# final_board.net
KiCad netlist of a schematic drawn in EAGLE
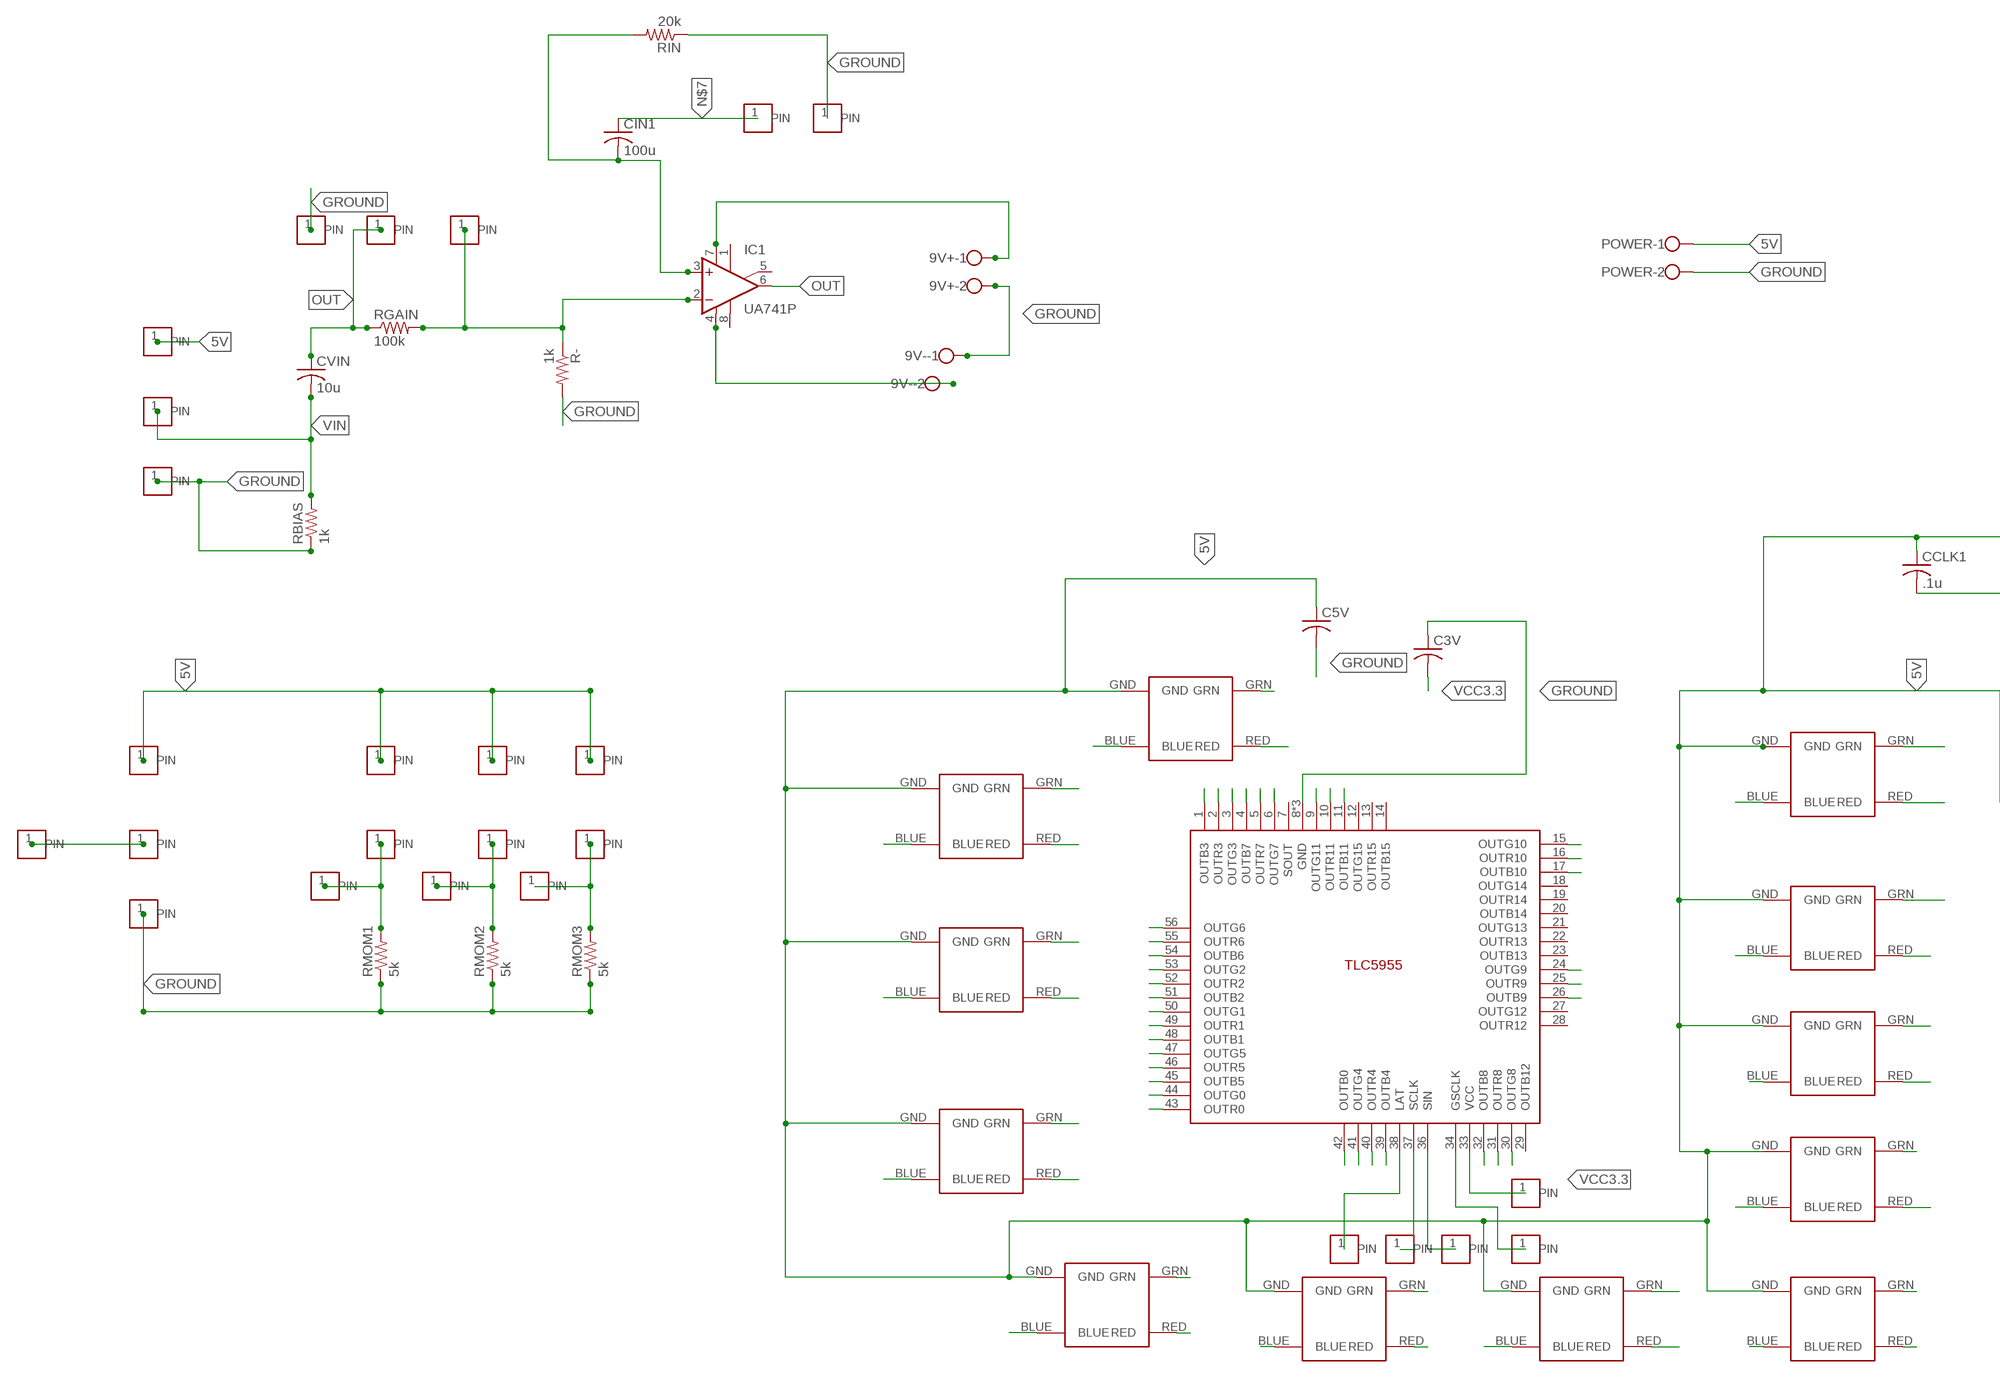
[diagram p0: schematic, sheet 1, part 1 of 2]
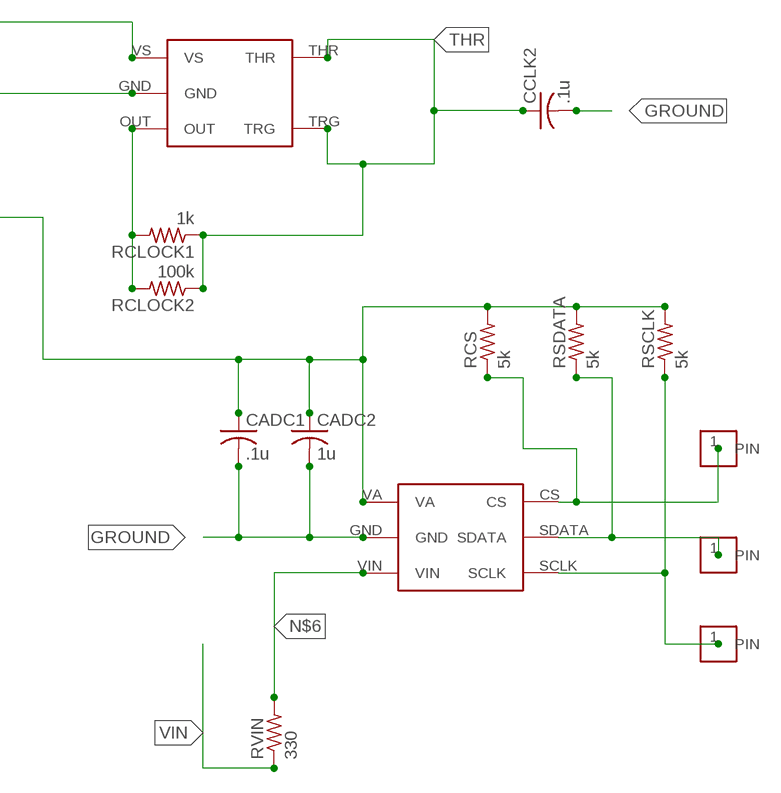
[diagram p1: schematic, sheet 1, part 2 of 2]

(export (version "E")
  (design (tool "Eeschema 10.0.6"))
  (components
    (comp (ref "3.3V")
      (value "HEADERPIN_1")
      (footprint "eagle-import:HEADERPIN_1")
      (libsource (lib "eagle-import") (part "HEADERPIN_1"))
    )
    (comp (ref "9V+")
      (value "W237-102")
      (footprint "eagle-import:W237-102")
      (fields (field (name "MPN") "237-102"))
      (libsource (lib "eagle-import") (part "W237-102"))
    )
    (comp (ref "9V-")
      (value "W237-102")
      (footprint "eagle-import:W237-102")
      (fields (field (name "MPN") "237-102"))
      (libsource (lib "eagle-import") (part "W237-102"))
    )
    (comp (ref "C3V")
      (value "C-USC0805")
      (footprint "eagle-import:C0805")
      (libsource (lib "eagle-import") (part "C-USC0805"))
    )
    (comp (ref "C5V")
      (value "C-USC0805")
      (footprint "eagle-import:C0805")
      (libsource (lib "eagle-import") (part "C-USC0805"))
    )
    (comp (ref "CADC1")
      (value ".1u")
      (footprint "eagle-import:C0805")
      (libsource (lib "eagle-import") (part "C-USC0805"))
    )
    (comp (ref "CADC2")
      (value "1u")
      (footprint "eagle-import:C0805")
      (libsource (lib "eagle-import") (part "C-USC0805"))
    )
    (comp (ref "CCLK1")
      (value ".1u")
      (footprint "eagle-import:C0805")
      (libsource (lib "eagle-import") (part "C-USC0805"))
    )
    (comp (ref "CCLK2")
      (value ".1u")
      (footprint "eagle-import:C0805")
      (libsource (lib "eagle-import") (part "C-USC0805"))
    )
    (comp (ref "CIN1")
      (value "100u")
      (footprint "eagle-import:C0805")
      (libsource (lib "eagle-import") (part "C-USC0805"))
    )
    (comp (ref "CS")
      (value "HEADERPIN_1")
      (footprint "eagle-import:HEADERPIN_1")
      (libsource (lib "eagle-import") (part "HEADERPIN_1"))
    )
    (comp (ref "CVIN")
      (value "10u")
      (footprint "eagle-import:C0805")
      (libsource (lib "eagle-import") (part "C-USC0805"))
    )
    (comp (ref "DATA")
      (value "HEADERPIN_1")
      (footprint "eagle-import:HEADERPIN_1")
      (libsource (lib "eagle-import") (part "HEADERPIN_1"))
    )
    (comp (ref "GSCLK")
      (value "HEADERPIN_1")
      (footprint "eagle-import:HEADERPIN_1")
      (libsource (lib "eagle-import") (part "HEADERPIN_1"))
    )
    (comp (ref "IC1")
      (value "UA741P")
      (footprint "eagle-import:DIL08")
      (libsource (lib "eagle-import") (part "741PUA"))
    )
    (comp (ref "INPUTGND")
      (value "HEADERPIN_1")
      (footprint "eagle-import:HEADERPIN_1")
      (libsource (lib "eagle-import") (part "HEADERPIN_1"))
    )
    (comp (ref "INPUTV")
      (value "HEADERPIN_1")
      (footprint "eagle-import:HEADERPIN_1")
      (libsource (lib "eagle-import") (part "HEADERPIN_1"))
    )
    (comp (ref "INT1")
      (value "HEADERPIN_1")
      (footprint "eagle-import:HEADERPIN_1")
      (libsource (lib "eagle-import") (part "HEADERPIN_1"))
    )
    (comp (ref "INT2")
      (value "HEADERPIN_1")
      (footprint "eagle-import:HEADERPIN_1")
      (libsource (lib "eagle-import") (part "HEADERPIN_1"))
    )
    (comp (ref "INT3")
      (value "HEADERPIN_1")
      (footprint "eagle-import:HEADERPIN_1")
      (libsource (lib "eagle-import") (part "HEADERPIN_1"))
    )
    (comp (ref "LAT")
      (value "HEADERPIN_1")
      (footprint "eagle-import:HEADERPIN_1")
      (libsource (lib "eagle-import") (part "HEADERPIN_1"))
    )
    (comp (ref "MOMA1")
      (value "HEADERPIN_1")
      (footprint "eagle-import:HEADERPIN_1")
      (libsource (lib "eagle-import") (part "HEADERPIN_1"))
    )
    (comp (ref "MOMA2")
      (value "HEADERPIN_1")
      (footprint "eagle-import:HEADERPIN_1")
      (libsource (lib "eagle-import") (part "HEADERPIN_1"))
    )
    (comp (ref "MOMA3")
      (value "HEADERPIN_1")
      (footprint "eagle-import:HEADERPIN_1")
      (libsource (lib "eagle-import") (part "HEADERPIN_1"))
    )
    (comp (ref "MOMB1")
      (value "HEADERPIN_1")
      (footprint "eagle-import:HEADERPIN_1")
      (libsource (lib "eagle-import") (part "HEADERPIN_1"))
    )
    (comp (ref "MOMB2")
      (value "HEADERPIN_1")
      (footprint "eagle-import:HEADERPIN_1")
      (libsource (lib "eagle-import") (part "HEADERPIN_1"))
    )
    (comp (ref "MOMB3")
      (value "HEADERPIN_1")
      (footprint "eagle-import:HEADERPIN_1")
      (libsource (lib "eagle-import") (part "HEADERPIN_1"))
    )
    (comp (ref "POTAMPGND")
      (value "HEADERPIN_1")
      (footprint "eagle-import:HEADERPIN_1")
      (libsource (lib "eagle-import") (part "HEADERPIN_1"))
    )
    (comp (ref "POTAMPVAL")
      (value "HEADERPIN_1")
      (footprint "eagle-import:HEADERPIN_1")
      (libsource (lib "eagle-import") (part "HEADERPIN_1"))
    )
    (comp (ref "POTAMPVCC")
      (value "HEADERPIN_1")
      (footprint "eagle-import:HEADERPIN_1")
      (libsource (lib "eagle-import") (part "HEADERPIN_1"))
    )
    (comp (ref "POTBIAS5V")
      (value "HEADERPIN_1")
      (footprint "eagle-import:HEADERPIN_1")
      (libsource (lib "eagle-import") (part "HEADERPIN_1"))
    )
    (comp (ref "POTBIASGND")
      (value "HEADERPIN_1")
      (footprint "eagle-import:HEADERPIN_1")
      (libsource (lib "eagle-import") (part "HEADERPIN_1"))
    )
    (comp (ref "POTBIASVAL")
      (value "HEADERPIN_1")
      (footprint "eagle-import:HEADERPIN_1")
      (libsource (lib "eagle-import") (part "HEADERPIN_1"))
    )
    (comp (ref "POTLVL5V")
      (value "HEADERPIN_1")
      (footprint "eagle-import:HEADERPIN_1")
      (libsource (lib "eagle-import") (part "HEADERPIN_1"))
    )
    (comp (ref "POTLVLGND")
      (value "HEADERPIN_1")
      (footprint "eagle-import:HEADERPIN_1")
      (libsource (lib "eagle-import") (part "HEADERPIN_1"))
    )
    (comp (ref "POTLVLVAL")
      (value "HEADERPIN_1")
      (footprint "eagle-import:HEADERPIN_1")
      (libsource (lib "eagle-import") (part "HEADERPIN_1"))
    )
    (comp (ref "POTLVLVAL2")
      (value "HEADERPIN_1")
      (footprint "eagle-import:HEADERPIN_1")
      (libsource (lib "eagle-import") (part "HEADERPIN_1"))
    )
    (comp (ref "POWER")
      (value "W237-102")
      (footprint "eagle-import:W237-102")
      (fields (field (name "MPN") "237-102"))
      (libsource (lib "eagle-import") (part "W237-102"))
    )
    (comp (ref "R-")
      (value "1k")
      (footprint "eagle-import:M0805")
      (libsource (lib "eagle-import") (part "R-US_M0805"))
    )
    (comp (ref "RBIAS")
      (value "1k")
      (footprint "eagle-import:M0805")
      (libsource (lib "eagle-import") (part "R-US_M0805"))
    )
    (comp (ref "RCLOCK1")
      (value "1k")
      (footprint "eagle-import:M0805")
      (libsource (lib "eagle-import") (part "R-US_M0805"))
    )
    (comp (ref "RCLOCK2")
      (value "100k")
      (footprint "eagle-import:M0805")
      (libsource (lib "eagle-import") (part "R-US_M0805"))
    )
    (comp (ref "RCS")
      (value "5k")
      (footprint "eagle-import:M0805")
      (libsource (lib "eagle-import") (part "R-US_M0805"))
    )
    (comp (ref "RGAIN")
      (value "100k")
      (footprint "eagle-import:M0805")
      (libsource (lib "eagle-import") (part "R-US_M0805"))
    )
    (comp (ref "RIN")
      (value "20k")
      (footprint "eagle-import:M0805")
      (libsource (lib "eagle-import") (part "R-US_M0805"))
    )
    (comp (ref "RMOM1")
      (value "5k")
      (footprint "eagle-import:M0805")
      (libsource (lib "eagle-import") (part "R-US_M0805"))
    )
    (comp (ref "RMOM2")
      (value "5k")
      (footprint "eagle-import:M0805")
      (libsource (lib "eagle-import") (part "R-US_M0805"))
    )
    (comp (ref "RMOM3")
      (value "5k")
      (footprint "eagle-import:M0805")
      (libsource (lib "eagle-import") (part "R-US_M0805"))
    )
    (comp (ref "RSCLK")
      (value "5k")
      (footprint "eagle-import:M0805")
      (libsource (lib "eagle-import") (part "R-US_M0805"))
    )
    (comp (ref "RSDATA")
      (value "5k")
      (footprint "eagle-import:M0805")
      (libsource (lib "eagle-import") (part "R-US_M0805"))
    )
    (comp (ref "RVIN")
      (value "330")
      (footprint "eagle-import:M0805")
      (libsource (lib "eagle-import") (part "R-US_M0805"))
    )
    (comp (ref "SCLK")
      (value "HEADERPIN_1")
      (footprint "eagle-import:HEADERPIN_1")
      (libsource (lib "eagle-import") (part "HEADERPIN_1"))
    )
    (comp (ref "SIN")
      (value "HEADERPIN_1")
      (footprint "eagle-import:HEADERPIN_1")
      (libsource (lib "eagle-import") (part "HEADERPIN_1"))
    )
    (comp (ref "SLK")
      (value "HEADERPIN_1")
      (footprint "eagle-import:HEADERPIN_1")
      (libsource (lib "eagle-import") (part "HEADERPIN_1"))
    )
    (comp (ref "TLC5955")
      (value "TLC5954")
      (footprint "eagle-import:TLC5955")
      (libsource (lib "eagle-import") (part "TLC5954"))
    )
    (comp (ref "U$1")
      (value "MIC1555")
      (footprint "eagle-import:SOT-23")
      (libsource (lib "eagle-import") (part "MIC1555"))
    )
    (comp (ref "U$2")
      (value "KINGSBRIGHT_LED_3.5X2.8")
      (footprint "eagle-import:KINGSBRIGHT_LED_3.5X2.8")
      (libsource (lib "eagle-import") (part "KINGSBRIGHT_LED_3.5X2.8"))
    )
    (comp (ref "U$3")
      (value "KINGSBRIGHT_LED_3.5X2.8")
      (footprint "eagle-import:KINGSBRIGHT_LED_3.5X2.8")
      (libsource (lib "eagle-import") (part "KINGSBRIGHT_LED_3.5X2.8"))
    )
    (comp (ref "U$4")
      (value "KINGSBRIGHT_LED_3.5X2.8")
      (footprint "eagle-import:KINGSBRIGHT_LED_3.5X2.8")
      (libsource (lib "eagle-import") (part "KINGSBRIGHT_LED_3.5X2.8"))
    )
    (comp (ref "U$5")
      (value "KINGSBRIGHT_LED_3.5X2.8")
      (footprint "eagle-import:KINGSBRIGHT_LED_3.5X2.8")
      (libsource (lib "eagle-import") (part "KINGSBRIGHT_LED_3.5X2.8"))
    )
    (comp (ref "U$6")
      (value "KINGSBRIGHT_LED_3.5X2.8")
      (footprint "eagle-import:KINGSBRIGHT_LED_3.5X2.8")
      (libsource (lib "eagle-import") (part "KINGSBRIGHT_LED_3.5X2.8"))
    )
    (comp (ref "U$7")
      (value "KINGSBRIGHT_LED_3.5X2.8")
      (footprint "eagle-import:KINGSBRIGHT_LED_3.5X2.8")
      (libsource (lib "eagle-import") (part "KINGSBRIGHT_LED_3.5X2.8"))
    )
    (comp (ref "U$8")
      (value "KINGSBRIGHT_LED_3.5X2.8")
      (footprint "eagle-import:KINGSBRIGHT_LED_3.5X2.8")
      (libsource (lib "eagle-import") (part "KINGSBRIGHT_LED_3.5X2.8"))
    )
    (comp (ref "U$9")
      (value "KINGSBRIGHT_LED_3.5X2.8")
      (footprint "eagle-import:KINGSBRIGHT_LED_3.5X2.8")
      (libsource (lib "eagle-import") (part "KINGSBRIGHT_LED_3.5X2.8"))
    )
    (comp (ref "U$10")
      (value "KINGSBRIGHT_LED_3.5X2.8")
      (footprint "eagle-import:KINGSBRIGHT_LED_3.5X2.8")
      (libsource (lib "eagle-import") (part "KINGSBRIGHT_LED_3.5X2.8"))
    )
    (comp (ref "U$11")
      (value "KINGSBRIGHT_LED_3.5X2.8")
      (footprint "eagle-import:KINGSBRIGHT_LED_3.5X2.8")
      (libsource (lib "eagle-import") (part "KINGSBRIGHT_LED_3.5X2.8"))
    )
    (comp (ref "U$12")
      (value "KINGSBRIGHT_LED_3.5X2.8")
      (footprint "eagle-import:KINGSBRIGHT_LED_3.5X2.8")
      (libsource (lib "eagle-import") (part "KINGSBRIGHT_LED_3.5X2.8"))
    )
    (comp (ref "U$13")
      (value "KINGSBRIGHT_LED_3.5X2.8")
      (footprint "eagle-import:KINGSBRIGHT_LED_3.5X2.8")
      (libsource (lib "eagle-import") (part "KINGSBRIGHT_LED_3.5X2.8"))
    )
    (comp (ref "U$14")
      (value "ADC121S101")
      (footprint "eagle-import:SOT-23(6)")
      (libsource (lib "eagle-import") (part "ADC121S101"))
    )
  )
  (nets
    (net (code "1") (name "/B0") (class "Default")
      (node (ref "TLC5955") (pin "42") (pinfunction "OUTB0_42") (pintype "bidirectional"))
      (node (ref "U$13") (pin "BLUE") (pinfunction "BLUE_BLUE") (pintype "bidirectional"))
    )
    (net (code "2") (name "/B1") (class "Default")
      (node (ref "TLC5955") (pin "48") (pinfunction "OUTB1_48") (pintype "bidirectional"))
      (node (ref "U$12") (pin "BLUE") (pinfunction "BLUE_BLUE") (pintype "bidirectional"))
    )
    (net (code "3") (name "/B2") (class "Default")
      (node (ref "TLC5955") (pin "51") (pinfunction "OUTB2_51") (pintype "bidirectional"))
      (node (ref "U$11") (pin "BLUE") (pinfunction "BLUE_BLUE") (pintype "bidirectional"))
    )
    (net (code "4") (name "/B3") (class "Default")
      (node (ref "TLC5955") (pin "1") (pinfunction "OUTB3_1") (pintype "bidirectional"))
      (node (ref "U$10") (pin "BLUE") (pinfunction "BLUE_BLUE") (pintype "bidirectional"))
    )
    (net (code "5") (name "/B4") (class "Default")
      (node (ref "TLC5955") (pin "39") (pinfunction "OUTB4_39") (pintype "bidirectional"))
      (node (ref "U$9") (pin "BLUE") (pinfunction "BLUE_BLUE") (pintype "bidirectional"))
    )
    (net (code "6") (name "/B5") (class "Default")
      (node (ref "TLC5955") (pin "45") (pinfunction "OUTB5_45") (pintype "bidirectional"))
      (node (ref "U$8") (pin "BLUE") (pinfunction "BLUE_BLUE") (pintype "bidirectional"))
    )
    (net (code "7") (name "/B6") (class "Default")
      (node (ref "TLC5955") (pin "54") (pinfunction "OUTB6_54") (pintype "bidirectional"))
      (node (ref "U$7") (pin "BLUE") (pinfunction "BLUE_BLUE") (pintype "bidirectional"))
    )
    (net (code "8") (name "/B7") (class "Default")
      (node (ref "TLC5955") (pin "4") (pinfunction "OUTB7_4") (pintype "bidirectional"))
      (node (ref "U$6") (pin "BLUE") (pinfunction "BLUE_BLUE") (pintype "bidirectional"))
    )
    (net (code "9") (name "/B8") (class "Default")
      (node (ref "TLC5955") (pin "32") (pinfunction "OUTB8_32") (pintype "bidirectional"))
      (node (ref "U$5") (pin "BLUE") (pinfunction "BLUE_BLUE") (pintype "bidirectional"))
    )
    (net (code "10") (name "/B9") (class "Default")
      (node (ref "TLC5955") (pin "26") (pinfunction "OUTB9_26") (pintype "bidirectional"))
      (node (ref "U$4") (pin "BLUE") (pinfunction "BLUE_BLUE") (pintype "bidirectional"))
    )
    (net (code "11") (name "/B10") (class "Default")
      (node (ref "TLC5955") (pin "17") (pinfunction "OUTB10_17") (pintype "bidirectional"))
      (node (ref "U$3") (pin "BLUE") (pinfunction "BLUE_BLUE") (pintype "bidirectional"))
    )
    (net (code "12") (name "/B11") (class "Default")
      (node (ref "TLC5955") (pin "11") (pinfunction "OUTB11_11") (pintype "bidirectional"))
      (node (ref "U$2") (pin "BLUE") (pinfunction "BLUE_BLUE") (pintype "bidirectional"))
    )
    (net (code "13") (name "/G0") (class "Default")
      (node (ref "TLC5955") (pin "44") (pinfunction "OUTG0_44") (pintype "bidirectional"))
      (node (ref "U$13") (pin "GRN") (pinfunction "GRN_GRN") (pintype "bidirectional"))
    )
    (net (code "14") (name "/G1") (class "Default")
      (node (ref "TLC5955") (pin "50") (pinfunction "OUTG1_50") (pintype "bidirectional"))
      (node (ref "U$12") (pin "GRN") (pinfunction "GRN_GRN") (pintype "bidirectional"))
    )
    (net (code "15") (name "/G2") (class "Default")
      (node (ref "TLC5955") (pin "53") (pinfunction "OUTG2_53") (pintype "bidirectional"))
      (node (ref "U$11") (pin "GRN") (pinfunction "GRN_GRN") (pintype "bidirectional"))
    )
    (net (code "16") (name "/G3") (class "Default")
      (node (ref "TLC5955") (pin "3") (pinfunction "OUTG3_3") (pintype "bidirectional"))
      (node (ref "U$10") (pin "GRN") (pinfunction "GRN_GRN") (pintype "bidirectional"))
    )
    (net (code "17") (name "/G4") (class "Default")
      (node (ref "TLC5955") (pin "41") (pinfunction "OUTG4_41") (pintype "bidirectional"))
      (node (ref "U$9") (pin "GRN") (pinfunction "GRN_GRN") (pintype "bidirectional"))
    )
    (net (code "18") (name "/G5") (class "Default")
      (node (ref "TLC5955") (pin "47") (pinfunction "OUTG5_47") (pintype "bidirectional"))
      (node (ref "U$8") (pin "GRN") (pinfunction "GRN_GRN") (pintype "bidirectional"))
    )
    (net (code "19") (name "/G6") (class "Default")
      (node (ref "TLC5955") (pin "56") (pinfunction "OUTG6_56") (pintype "bidirectional"))
      (node (ref "U$7") (pin "GRN") (pinfunction "GRN_GRN") (pintype "bidirectional"))
    )
    (net (code "20") (name "/G7") (class "Default")
      (node (ref "TLC5955") (pin "6") (pinfunction "OUTG7_6") (pintype "bidirectional"))
      (node (ref "U$6") (pin "GRN") (pinfunction "GRN_GRN") (pintype "bidirectional"))
    )
    (net (code "21") (name "/G8") (class "Default")
      (node (ref "TLC5955") (pin "30") (pinfunction "OUTG8_30") (pintype "bidirectional"))
      (node (ref "U$5") (pin "GRN") (pinfunction "GRN_GRN") (pintype "bidirectional"))
    )
    (net (code "22") (name "/G9") (class "Default")
      (node (ref "TLC5955") (pin "24") (pinfunction "OUTG9_24") (pintype "bidirectional"))
      (node (ref "U$4") (pin "GRN") (pinfunction "GRN_GRN") (pintype "bidirectional"))
    )
    (net (code "23") (name "/G10") (class "Default")
      (node (ref "TLC5955") (pin "15") (pinfunction "OUTG10_15") (pintype "bidirectional"))
      (node (ref "U$3") (pin "GRN") (pinfunction "GRN_GRN") (pintype "bidirectional"))
    )
    (net (code "24") (name "/G11") (class "Default")
      (node (ref "TLC5955") (pin "9") (pinfunction "OUTG11_9") (pintype "bidirectional"))
      (node (ref "U$2") (pin "GRN") (pinfunction "GRN_GRN") (pintype "bidirectional"))
    )
    (net (code "25") (name "/GSCLK") (class "Default")
      (node (ref "GSCLK") (pin "1") (pinfunction "PIN_1") (pintype "bidirectional"))
      (node (ref "RCLOCK1") (pin "2") (pinfunction "2_2") (pintype "passive"))
      (node (ref "RCLOCK2") (pin "2") (pinfunction "2_2") (pintype "passive"))
      (node (ref "TLC5955") (pin "34") (pinfunction "GSCLK_34") (pintype "bidirectional"))
      (node (ref "U$1") (pin "OUT") (pinfunction "OUT_OUT") (pintype "bidirectional"))
    )
    (net (code "26") (name "/R0") (class "Default")
      (node (ref "TLC5955") (pin "43") (pinfunction "OUTR0_43") (pintype "bidirectional"))
      (node (ref "U$13") (pin "RED") (pinfunction "RED_RED") (pintype "bidirectional"))
    )
    (net (code "27") (name "/R1") (class "Default")
      (node (ref "TLC5955") (pin "49") (pinfunction "OUTR1_49") (pintype "bidirectional"))
      (node (ref "U$12") (pin "RED") (pinfunction "RED_RED") (pintype "bidirectional"))
    )
    (net (code "28") (name "/R2") (class "Default")
      (node (ref "TLC5955") (pin "52") (pinfunction "OUTR2_52") (pintype "bidirectional"))
      (node (ref "U$11") (pin "RED") (pinfunction "RED_RED") (pintype "bidirectional"))
    )
    (net (code "29") (name "/R3") (class "Default")
      (node (ref "TLC5955") (pin "2") (pinfunction "OUTR3_2") (pintype "bidirectional"))
      (node (ref "U$10") (pin "RED") (pinfunction "RED_RED") (pintype "bidirectional"))
    )
    (net (code "30") (name "/R4") (class "Default")
      (node (ref "TLC5955") (pin "40") (pinfunction "OUTR4_40") (pintype "bidirectional"))
      (node (ref "U$9") (pin "RED") (pinfunction "RED_RED") (pintype "bidirectional"))
    )
    (net (code "31") (name "/R5") (class "Default")
      (node (ref "TLC5955") (pin "46") (pinfunction "OUTR5_46") (pintype "bidirectional"))
      (node (ref "U$8") (pin "RED") (pinfunction "RED_RED") (pintype "bidirectional"))
    )
    (net (code "32") (name "/R6") (class "Default")
      (node (ref "TLC5955") (pin "55") (pinfunction "OUTR6_55") (pintype "bidirectional"))
      (node (ref "U$7") (pin "RED") (pinfunction "RED_RED") (pintype "bidirectional"))
    )
    (net (code "33") (name "/R7") (class "Default")
      (node (ref "TLC5955") (pin "5") (pinfunction "OUTR7_5") (pintype "bidirectional"))
      (node (ref "U$6") (pin "RED") (pinfunction "RED_RED") (pintype "bidirectional"))
    )
    (net (code "34") (name "/R8") (class "Default")
      (node (ref "TLC5955") (pin "31") (pinfunction "OUTR8_31") (pintype "bidirectional"))
      (node (ref "U$5") (pin "RED") (pinfunction "RED_RED") (pintype "bidirectional"))
    )
    (net (code "35") (name "/R9") (class "Default")
      (node (ref "TLC5955") (pin "25") (pinfunction "OUTR9_25") (pintype "bidirectional"))
      (node (ref "U$4") (pin "RED") (pinfunction "RED_RED") (pintype "bidirectional"))
    )
    (net (code "36") (name "/R10") (class "Default")
      (node (ref "TLC5955") (pin "16") (pinfunction "OUTR10_16") (pintype "bidirectional"))
      (node (ref "U$3") (pin "RED") (pinfunction "RED_RED") (pintype "bidirectional"))
    )
    (net (code "37") (name "/R11") (class "Default")
      (node (ref "TLC5955") (pin "10") (pinfunction "OUTR11_10") (pintype "bidirectional"))
      (node (ref "U$2") (pin "RED") (pinfunction "RED_RED") (pintype "bidirectional"))
    )
    (net (code "38") (name "5V") (class "Default")
      (node (ref "C5V") (pin "1") (pinfunction "1_1") (pintype "passive"))
      (node (ref "CADC1") (pin "1") (pinfunction "1_1") (pintype "passive"))
      (node (ref "CADC2") (pin "1") (pinfunction "1_1") (pintype "passive"))
      (node (ref "CCLK1") (pin "1") (pinfunction "1_1") (pintype "passive"))
      (node (ref "MOMA1") (pin "1") (pinfunction "PIN_1") (pintype "bidirectional"))
      (node (ref "MOMA2") (pin "1") (pinfunction "PIN_1") (pintype "bidirectional"))
      (node (ref "MOMA3") (pin "1") (pinfunction "PIN_1") (pintype "bidirectional"))
      (node (ref "POTBIAS5V") (pin "1") (pinfunction "PIN_1") (pintype "bidirectional"))
      (node (ref "POTLVL5V") (pin "1") (pinfunction "PIN_1") (pintype "bidirectional"))
      (node (ref "POWER") (pin "1") (pinfunction "KL_1") (pintype "passive"))
      (node (ref "RCS") (pin "2") (pinfunction "2_2") (pintype "passive"))
      (node (ref "RSCLK") (pin "2") (pinfunction "2_2") (pintype "passive"))
      (node (ref "RSDATA") (pin "2") (pinfunction "2_2") (pintype "passive"))
      (node (ref "U$1") (pin "VS") (pinfunction "VS_VS") (pintype "bidirectional"))
      (node (ref "U$10") (pin "GND") (pinfunction "GND_GND") (pintype "bidirectional"))
      (node (ref "U$11") (pin "GND") (pinfunction "GND_GND") (pintype "bidirectional"))
      (node (ref "U$12") (pin "GND") (pinfunction "GND_GND") (pintype "bidirectional"))
      (node (ref "U$13") (pin "GND") (pinfunction "GND_GND") (pintype "bidirectional"))
      (node (ref "U$14") (pin "VA") (pinfunction "VA_VA") (pintype "bidirectional"))
      (node (ref "U$2") (pin "GND") (pinfunction "GND_GND") (pintype "bidirectional"))
      (node (ref "U$3") (pin "GND") (pinfunction "GND_GND") (pintype "bidirectional"))
      (node (ref "U$4") (pin "GND") (pinfunction "GND_GND") (pintype "bidirectional"))
      (node (ref "U$5") (pin "GND") (pinfunction "GND_GND") (pintype "bidirectional"))
      (node (ref "U$6") (pin "GND") (pinfunction "GND_GND") (pintype "bidirectional"))
      (node (ref "U$7") (pin "GND") (pinfunction "GND_GND") (pintype "bidirectional"))
      (node (ref "U$8") (pin "GND") (pinfunction "GND_GND") (pintype "bidirectional"))
      (node (ref "U$9") (pin "GND") (pinfunction "GND_GND") (pintype "bidirectional"))
    )
    (net (code "39") (name "GROUND") (class "Default")
      (node (ref "9V+") (pin "2") (pinfunction "KL_2") (pintype "passive"))
      (node (ref "9V-") (pin "1") (pinfunction "KL_1") (pintype "passive"))
      (node (ref "C3V") (pin "1") (pinfunction "1_1") (pintype "passive"))
      (node (ref "C5V") (pin "2") (pinfunction "2_2") (pintype "passive"))
      (node (ref "CADC1") (pin "2") (pinfunction "2_2") (pintype "passive"))
      (node (ref "CADC2") (pin "2") (pinfunction "2_2") (pintype "passive"))
      (node (ref "CCLK1") (pin "2") (pinfunction "2_2") (pintype "passive"))
      (node (ref "CCLK2") (pin "2") (pinfunction "2_2") (pintype "passive"))
      (node (ref "INPUTGND") (pin "1") (pinfunction "PIN_1") (pintype "bidirectional"))
      (node (ref "POTAMPGND") (pin "1") (pinfunction "PIN_1") (pintype "bidirectional"))
      (node (ref "POTBIASGND") (pin "1") (pinfunction "PIN_1") (pintype "bidirectional"))
      (node (ref "POTLVLGND") (pin "1") (pinfunction "PIN_1") (pintype "bidirectional"))
      (node (ref "POWER") (pin "2") (pinfunction "KL_2") (pintype "passive"))
      (node (ref "R-") (pin "2") (pinfunction "2_2") (pintype "passive"))
      (node (ref "RBIAS") (pin "1") (pinfunction "1_1") (pintype "passive"))
      (node (ref "RIN") (pin "1") (pinfunction "1_1") (pintype "passive"))
      (node (ref "RMOM1") (pin "1") (pinfunction "1_1") (pintype "passive"))
      (node (ref "RMOM2") (pin "1") (pinfunction "1_1") (pintype "passive"))
      (node (ref "RMOM3") (pin "1") (pinfunction "1_1") (pintype "passive"))
      (node (ref "TLC5955") (pin "35") (pinfunction "GND_35") (pintype "bidirectional"))
      (node (ref "TLC5955") (pin "8") (pinfunction "GND_8") (pintype "bidirectional"))
      (node (ref "TLC5955") (pin "HEATSINK") (pinfunction "GND_HEATSINK") (pintype "bidirectional"))
      (node (ref "U$1") (pin "GND") (pinfunction "GND_GND") (pintype "bidirectional"))
      (node (ref "U$14") (pin "GND") (pinfunction "GND_GND") (pintype "bidirectional"))
    )
    (net (code "40") (name "N$6") (class "Default")
      (node (ref "RVIN") (pin "2") (pinfunction "2_2") (pintype "passive"))
      (node (ref "U$14") (pin "VIN") (pinfunction "VIN_VIN") (pintype "bidirectional"))
    )
    (net (code "41") (name "N$7") (class "Default")
      (node (ref "CIN1") (pin "1") (pinfunction "1_1") (pintype "passive"))
      (node (ref "INPUTV") (pin "1") (pinfunction "PIN_1") (pintype "bidirectional"))
    )
    (net (code "42") (name "Net-(9V+A-KL)") (class "Default")
      (node (ref "9V+") (pin "1") (pinfunction "KL_1") (pintype "passive"))
      (node (ref "IC1") (pin "7") (pinfunction "V+_7") (pintype "power_in"))
    )
    (net (code "43") (name "Net-(9V-B-KL)") (class "Default")
      (node (ref "9V-") (pin "2") (pinfunction "KL_2") (pintype "passive"))
      (node (ref "IC1") (pin "4") (pinfunction "V-_4") (pintype "power_in"))
    )
    (net (code "44") (name "Net-(CS-PIN)") (class "Default")
      (node (ref "CS") (pin "1") (pinfunction "PIN_1") (pintype "bidirectional"))
      (node (ref "RCS") (pin "1") (pinfunction "1_1") (pintype "passive"))
      (node (ref "U$14") (pin "CS") (pinfunction "CS_CS") (pintype "bidirectional"))
    )
    (net (code "45") (name "Net-(DATA-PIN)") (class "Default")
      (node (ref "DATA") (pin "1") (pinfunction "PIN_1") (pintype "bidirectional"))
      (node (ref "RSDATA") (pin "1") (pinfunction "1_1") (pintype "passive"))
      (node (ref "U$14") (pin "SDATA") (pinfunction "SDATA_SDATA") (pintype "bidirectional"))
    )
    (net (code "46") (name "Net-(IC1-+IN)") (class "Default")
      (node (ref "CIN1") (pin "2") (pinfunction "2_2") (pintype "passive"))
      (node (ref "IC1") (pin "3") (pinfunction "+IN_3") (pintype "input"))
      (node (ref "RIN") (pin "2") (pinfunction "2_2") (pintype "passive"))
    )
    (net (code "47") (name "Net-(IC1--IN)") (class "Default")
      (node (ref "IC1") (pin "2") (pinfunction "-IN_2") (pintype "input"))
      (node (ref "POTAMPVCC") (pin "1") (pinfunction "PIN_1") (pintype "bidirectional"))
      (node (ref "R-") (pin "1") (pinfunction "1_1") (pintype "passive"))
      (node (ref "RGAIN") (pin "2") (pinfunction "2_2") (pintype "passive"))
    )
    (net (code "48") (name "Net-(INT1-PIN)") (class "Default")
      (node (ref "INT1") (pin "1") (pinfunction "PIN_1") (pintype "bidirectional"))
      (node (ref "MOMB1") (pin "1") (pinfunction "PIN_1") (pintype "bidirectional"))
      (node (ref "RMOM1") (pin "2") (pinfunction "2_2") (pintype "passive"))
    )
    (net (code "49") (name "Net-(INT2-PIN)") (class "Default")
      (node (ref "INT2") (pin "1") (pinfunction "PIN_1") (pintype "bidirectional"))
      (node (ref "MOMB2") (pin "1") (pinfunction "PIN_1") (pintype "bidirectional"))
      (node (ref "RMOM2") (pin "2") (pinfunction "2_2") (pintype "passive"))
    )
    (net (code "50") (name "Net-(INT3-PIN)") (class "Default")
      (node (ref "INT3") (pin "1") (pinfunction "PIN_1") (pintype "bidirectional"))
      (node (ref "MOMB3") (pin "1") (pinfunction "PIN_1") (pintype "bidirectional"))
      (node (ref "RMOM3") (pin "2") (pinfunction "2_2") (pintype "passive"))
    )
    (net (code "51") (name "Net-(LAT-PIN)") (class "Default")
      (node (ref "LAT") (pin "1") (pinfunction "PIN_1") (pintype "bidirectional"))
      (node (ref "TLC5955") (pin "38") (pinfunction "LAT_38") (pintype "bidirectional"))
    )
    (net (code "52") (name "Net-(POTLVLVAL-PIN)") (class "Default")
      (node (ref "POTLVLVAL") (pin "1") (pinfunction "PIN_1") (pintype "bidirectional"))
      (node (ref "POTLVLVAL2") (pin "1") (pinfunction "PIN_1") (pintype "bidirectional"))
    )
    (net (code "53") (name "Net-(SCLK-PIN)") (class "Default")
      (node (ref "SCLK") (pin "1") (pinfunction "PIN_1") (pintype "bidirectional"))
      (node (ref "TLC5955") (pin "37") (pinfunction "SCLK_37") (pintype "bidirectional"))
    )
    (net (code "54") (name "Net-(SIN-PIN)") (class "Default")
      (node (ref "SIN") (pin "1") (pinfunction "PIN_1") (pintype "bidirectional"))
      (node (ref "TLC5955") (pin "36") (pinfunction "SIN_36") (pintype "bidirectional"))
    )
    (net (code "55") (name "Net-(SLK-PIN)") (class "Default")
      (node (ref "RSCLK") (pin "1") (pinfunction "1_1") (pintype "passive"))
      (node (ref "SLK") (pin "1") (pinfunction "PIN_1") (pintype "bidirectional"))
      (node (ref "U$14") (pin "SCLK") (pinfunction "SCLK_SCLK") (pintype "bidirectional"))
    )
    (net (code "56") (name "OUT") (class "Default")
      (node (ref "CVIN") (pin "1") (pinfunction "1_1") (pintype "passive"))
      (node (ref "IC1") (pin "6") (pinfunction "OUT_6") (pintype "output"))
      (node (ref "POTAMPVAL") (pin "1") (pinfunction "PIN_1") (pintype "bidirectional"))
      (node (ref "RGAIN") (pin "1") (pinfunction "1_1") (pintype "passive"))
    )
    (net (code "57") (name "THR") (class "Default")
      (node (ref "CCLK2") (pin "1") (pinfunction "1_1") (pintype "passive"))
      (node (ref "RCLOCK1") (pin "1") (pinfunction "1_1") (pintype "passive"))
      (node (ref "RCLOCK2") (pin "1") (pinfunction "1_1") (pintype "passive"))
      (node (ref "U$1") (pin "THR") (pinfunction "THR_THR") (pintype "bidirectional"))
      (node (ref "U$1") (pin "TRG") (pinfunction "TRG_TRG") (pintype "bidirectional"))
    )
    (net (code "58") (name "VCC3.3") (class "Default")
      (node (ref "3.3V") (pin "1") (pinfunction "PIN_1") (pintype "bidirectional"))
      (node (ref "C3V") (pin "2") (pinfunction "2_2") (pintype "passive"))
      (node (ref "TLC5955") (pin "33") (pinfunction "VCC_33") (pintype "bidirectional"))
    )
    (net (code "59") (name "VIN") (class "Default")
      (node (ref "CVIN") (pin "2") (pinfunction "2_2") (pintype "passive"))
      (node (ref "POTBIASVAL") (pin "1") (pinfunction "PIN_1") (pintype "bidirectional"))
      (node (ref "RBIAS") (pin "2") (pinfunction "2_2") (pintype "passive"))
      (node (ref "RVIN") (pin "1") (pinfunction "1_1") (pintype "passive"))
    )
    (net (code "60") (name "unconnected-(IC1-ON1-Pad1)") (class "Default")
      (node (ref "IC1") (pin "1") (pinfunction "ON1_1") (pintype "passive"))
    )
    (net (code "61") (name "unconnected-(IC1-ON2-Pad5)") (class "Default")
      (node (ref "IC1") (pin "5") (pinfunction "ON2_5") (pintype "passive"))
    )
    (net (code "62") (name "unconnected-(IC1-OPT-Pad8)") (class "Default")
      (node (ref "IC1") (pin "8") (pinfunction "OPT_8") (pintype "passive"))
    )
    (net (code "63") (name "unconnected-(TLC5955-OUTB12-Pad29)") (class "Default")
      (node (ref "TLC5955") (pin "29") (pinfunction "OUTB12_29") (pintype "bidirectional"))
    )
    (net (code "64") (name "unconnected-(TLC5955-OUTB13-Pad23)") (class "Default")
      (node (ref "TLC5955") (pin "23") (pinfunction "OUTB13_23") (pintype "bidirectional"))
    )
    (net (code "65") (name "unconnected-(TLC5955-OUTB14-Pad20)") (class "Default")
      (node (ref "TLC5955") (pin "20") (pinfunction "OUTB14_20") (pintype "bidirectional"))
    )
    (net (code "66") (name "unconnected-(TLC5955-OUTB15-Pad14)") (class "Default")
      (node (ref "TLC5955") (pin "14") (pinfunction "OUTB15_14") (pintype "bidirectional"))
    )
    (net (code "67") (name "unconnected-(TLC5955-OUTG12-Pad27)") (class "Default")
      (node (ref "TLC5955") (pin "27") (pinfunction "OUTG12_27") (pintype "bidirectional"))
    )
    (net (code "68") (name "unconnected-(TLC5955-OUTG13-Pad21)") (class "Default")
      (node (ref "TLC5955") (pin "21") (pinfunction "OUTG13_21") (pintype "bidirectional"))
    )
    (net (code "69") (name "unconnected-(TLC5955-OUTG14-Pad18)") (class "Default")
      (node (ref "TLC5955") (pin "18") (pinfunction "OUTG14_18") (pintype "bidirectional"))
    )
    (net (code "70") (name "unconnected-(TLC5955-OUTG15-Pad12)") (class "Default")
      (node (ref "TLC5955") (pin "12") (pinfunction "OUTG15_12") (pintype "bidirectional"))
    )
    (net (code "71") (name "unconnected-(TLC5955-OUTR12-Pad28)") (class "Default")
      (node (ref "TLC5955") (pin "28") (pinfunction "OUTR12_28") (pintype "bidirectional"))
    )
    (net (code "72") (name "unconnected-(TLC5955-OUTR13-Pad22)") (class "Default")
      (node (ref "TLC5955") (pin "22") (pinfunction "OUTR13_22") (pintype "bidirectional"))
    )
    (net (code "73") (name "unconnected-(TLC5955-OUTR14-Pad19)") (class "Default")
      (node (ref "TLC5955") (pin "19") (pinfunction "OUTR14_19") (pintype "bidirectional"))
    )
    (net (code "74") (name "unconnected-(TLC5955-OUTR15-Pad13)") (class "Default")
      (node (ref "TLC5955") (pin "13") (pinfunction "OUTR15_13") (pintype "bidirectional"))
    )
    (net (code "75") (name "unconnected-(TLC5955-SOUT-Pad7)") (class "Default")
      (node (ref "TLC5955") (pin "7") (pinfunction "SOUT_7") (pintype "bidirectional"))
    )
  )
)
